# REGULATOR.net
KiCad netlist of a schematic drawn in Altium Designer
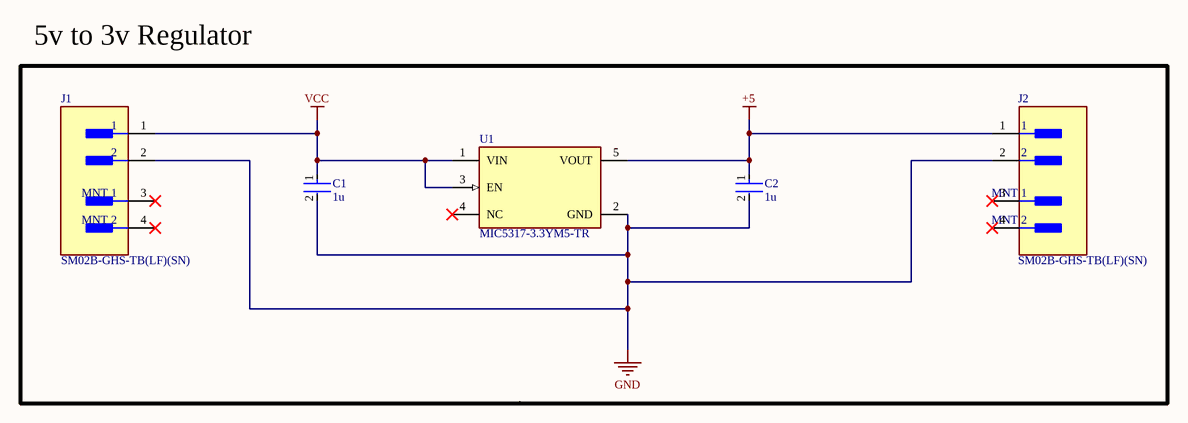
[diagram p0: REGULATOR.SchDoc]

(export (version "E")
  (design (tool "Eeschema 10.0.6"))
  (components
    (comp (ref "C1")
      (value "1u")
      (footprint "FP-CC0805-0_2-1_45-IPC_A")
      (description "CAP CER 10UF 10V X5R 0805")
      (fields (field (name "VOLTAGE") "10V") (field (name "TOLERANCE") "10%"))
      (libsource (lib "Altium Content Vault") (part "e9c51b7dd13d4faca003ae77663ab08"))
    )
    (comp (ref "C2")
      (value "1u")
      (footprint "FP-CC0805-0_2-1_45-IPC_A")
      (description "CAP CER 10UF 10V X5R 0805")
      (fields (field (name "VOLTAGE") "10V") (field (name "TOLERANCE") "10%"))
      (libsource (lib "Altium Content Vault") (part "e9c51b7dd13d4faca003ae77663ab08"))
    )
    (comp (ref "J1")
      (value "SM02B-GHS-TB(LF)(SN)")
      (footprint "FP-SM02B-GHS-TB_LF_SN-MFG")
      (description "CONN HEADER SMD R/A 2POS 1.25MM")
      (libsource (lib "") (part "56ec3178a87b3978bdc1b3682cd516a_1"))
    )
    (comp (ref "J2")
      (value "SM02B-GHS-TB(LF)(SN)")
      (footprint "FP-SM02B-GHS-TB_LF_SN-MFG")
      (description "CONN HEADER SMD R/A 2POS 1.25MM")
      (libsource (lib "Altium Content Vault") (part "56ec3178a87b3978bdc1b3682cd516a"))
    )
    (comp (ref "U1")
      (value "MIC5317-3.3YM5-TR")
      (footprint "FP-SOT23-5LD-PL-1-MFG")
      (description "IC REG LINEAR 3.3V 150MA SOT23-5")
      (libsource (lib "Altium Content Vault") (part "0a093dae7315cdc977fd108dde87457"))
    )
  )
  (nets
    (net (code "1") (name "+5") (class "Default")
      (node (ref "C2") (pin "1") (pinfunction "1_1") (pintype "passive"))
      (node (ref "J2") (pin "1") (pinfunction "1_1") (pintype "passive"))
      (node (ref "U1") (pin "5") (pinfunction "VOUT_5") (pintype "power_in"))
    )
    (net (code "2") (name "GND") (class "Default")
      (node (ref "C1") (pin "2") (pinfunction "2_2") (pintype "passive"))
      (node (ref "C2") (pin "2") (pinfunction "2_2") (pintype "passive"))
      (node (ref "J1") (pin "2") (pinfunction "2_2") (pintype "passive"))
      (node (ref "J2") (pin "2") (pinfunction "2_2") (pintype "passive"))
      (node (ref "U1") (pin "2") (pinfunction "GND_2") (pintype "power_in"))
    )
    (net (code "3") (name "VCC") (class "Default")
      (node (ref "C1") (pin "1") (pinfunction "1_1") (pintype "passive"))
      (node (ref "J1") (pin "1") (pinfunction "1_1") (pintype "passive"))
      (node (ref "U1") (pin "1") (pinfunction "VIN_1") (pintype "power_in"))
      (node (ref "U1") (pin "3") (pinfunction "EN_3") (pintype "input"))
    )
    (net (code "4") (name "unconnected-(J1-MNT_1-Pad3)") (class "Default")
      (node (ref "J1") (pin "3") (pinfunction "MNT_1_3") (pintype "passive+no_connect"))
    )
    (net (code "5") (name "unconnected-(J1-MNT_2-Pad4)") (class "Default")
      (node (ref "J1") (pin "4") (pinfunction "MNT_2_4") (pintype "passive+no_connect"))
    )
    (net (code "6") (name "unconnected-(J2-MNT_1-Pad3)") (class "Default")
      (node (ref "J2") (pin "3") (pinfunction "MNT_1_3") (pintype "passive+no_connect"))
    )
    (net (code "7") (name "unconnected-(J2-MNT_2-Pad4)") (class "Default")
      (node (ref "J2") (pin "4") (pinfunction "MNT_2_4") (pintype "passive+no_connect"))
    )
    (net (code "8") (name "unconnected-(U1-NC-Pad4)") (class "Default")
      (node (ref "U1") (pin "4") (pinfunction "NC_4") (pintype "passive+no_connect"))
    )
  )
)
